# servo.net
KiCad netlist of a schematic drawn in EAGLE
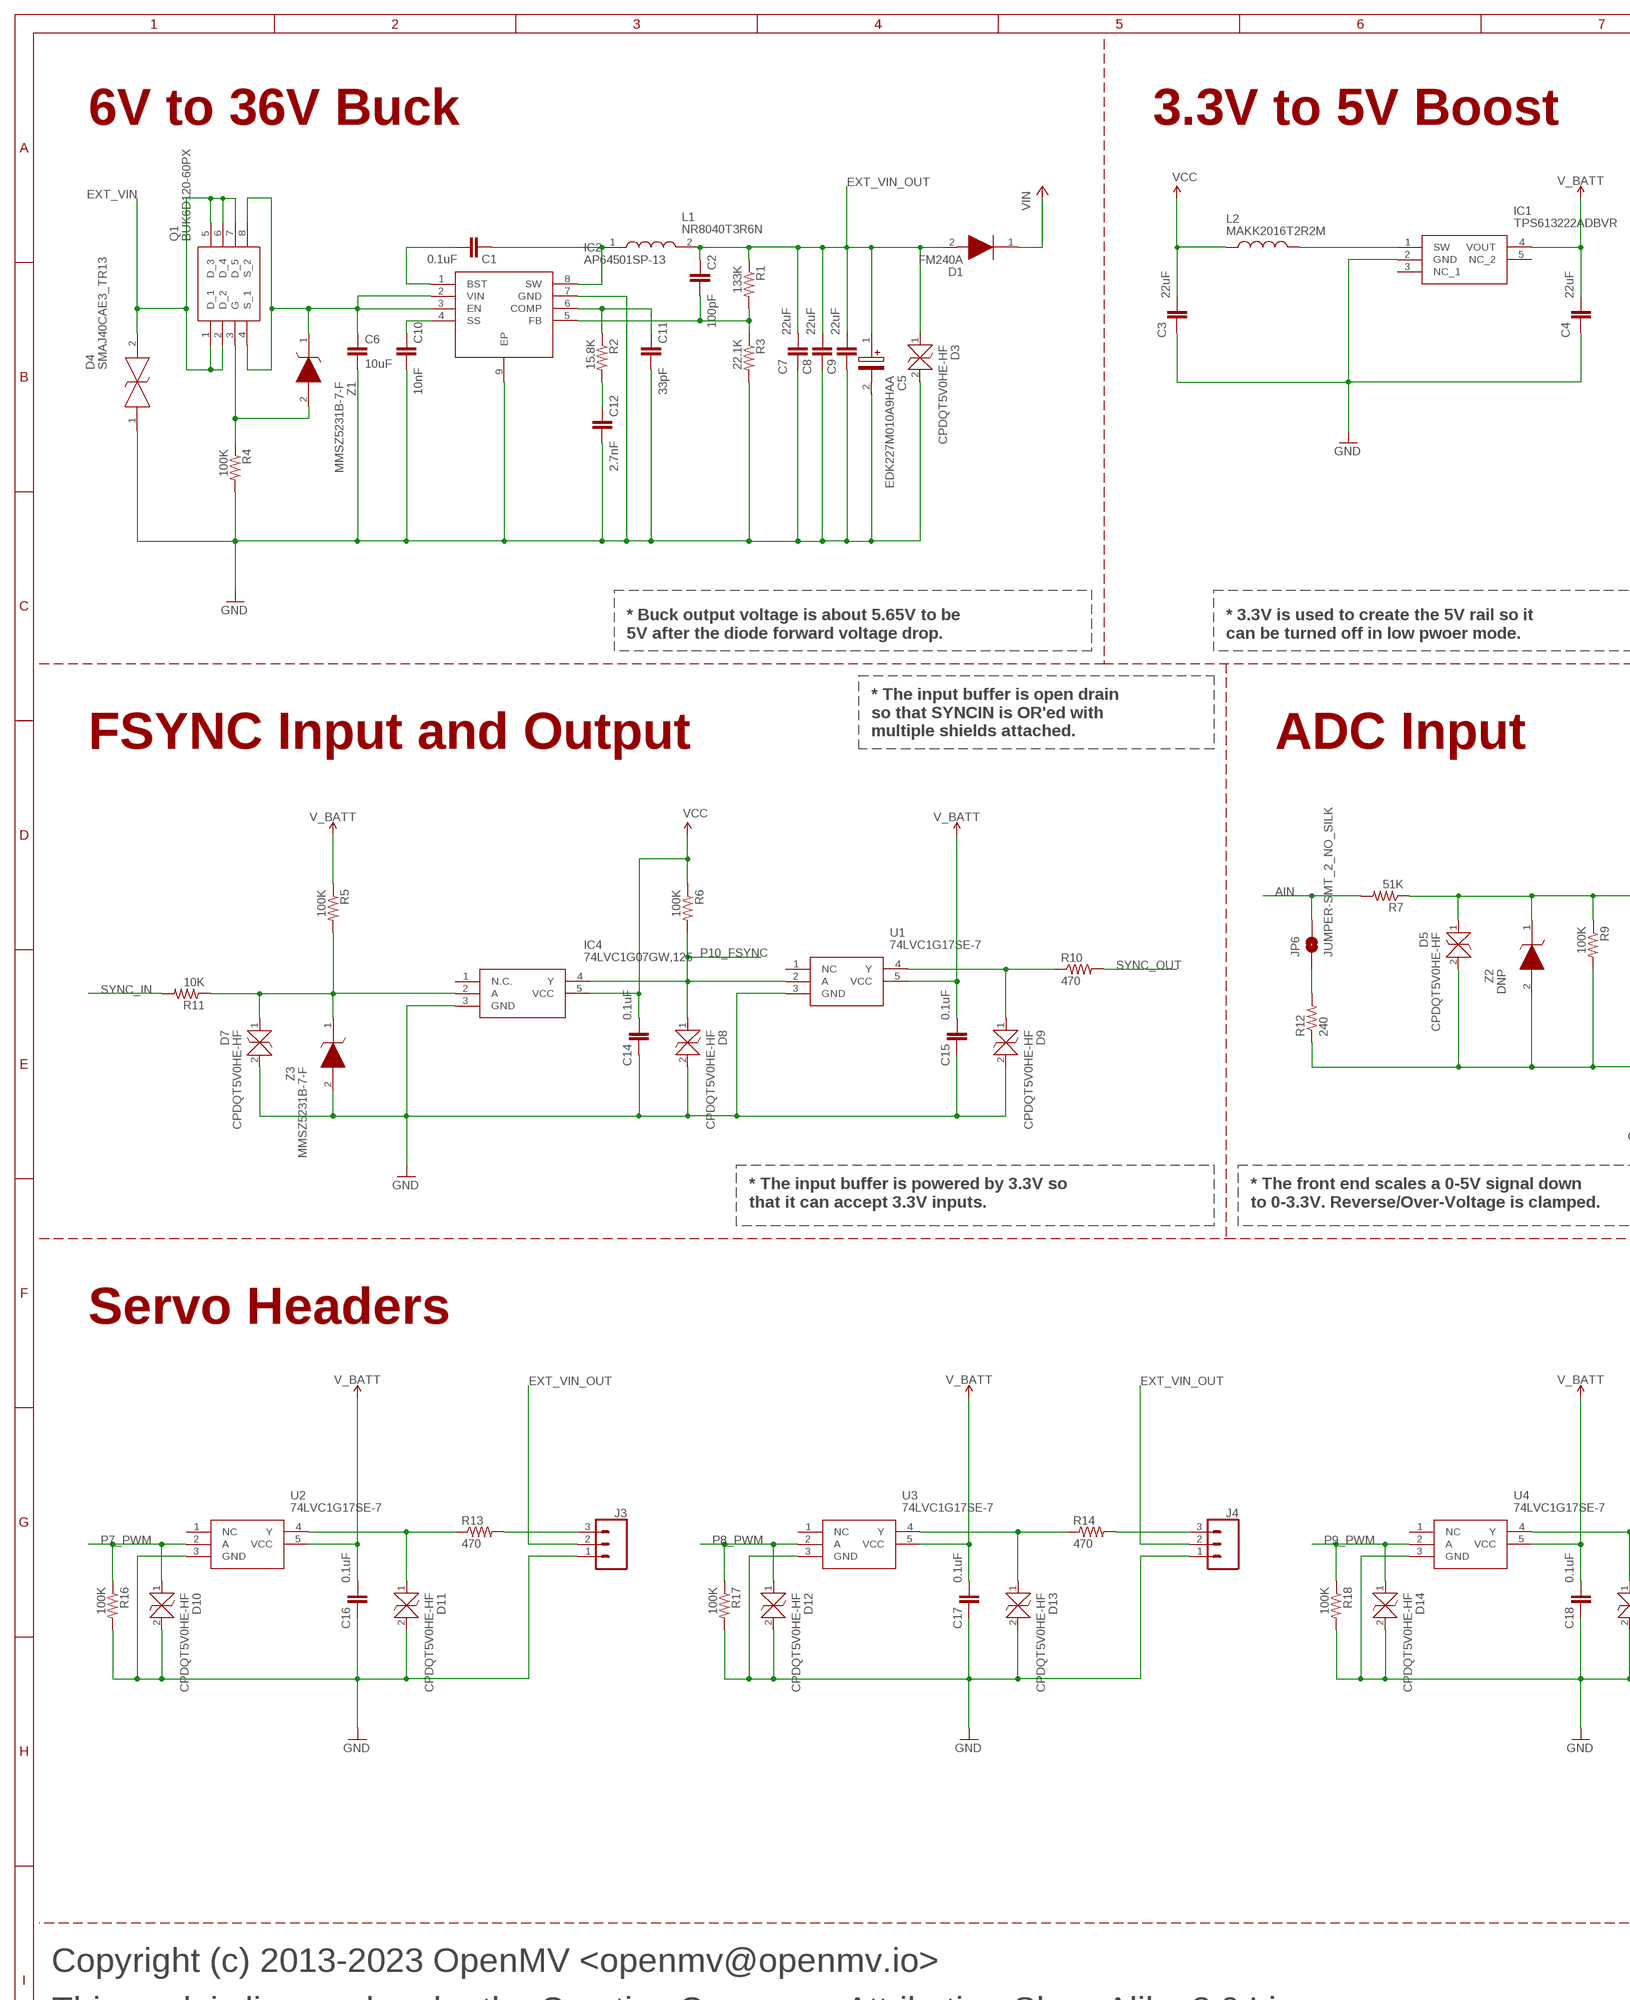
[diagram p0: schematic, sheet 1, part 1 of 2]
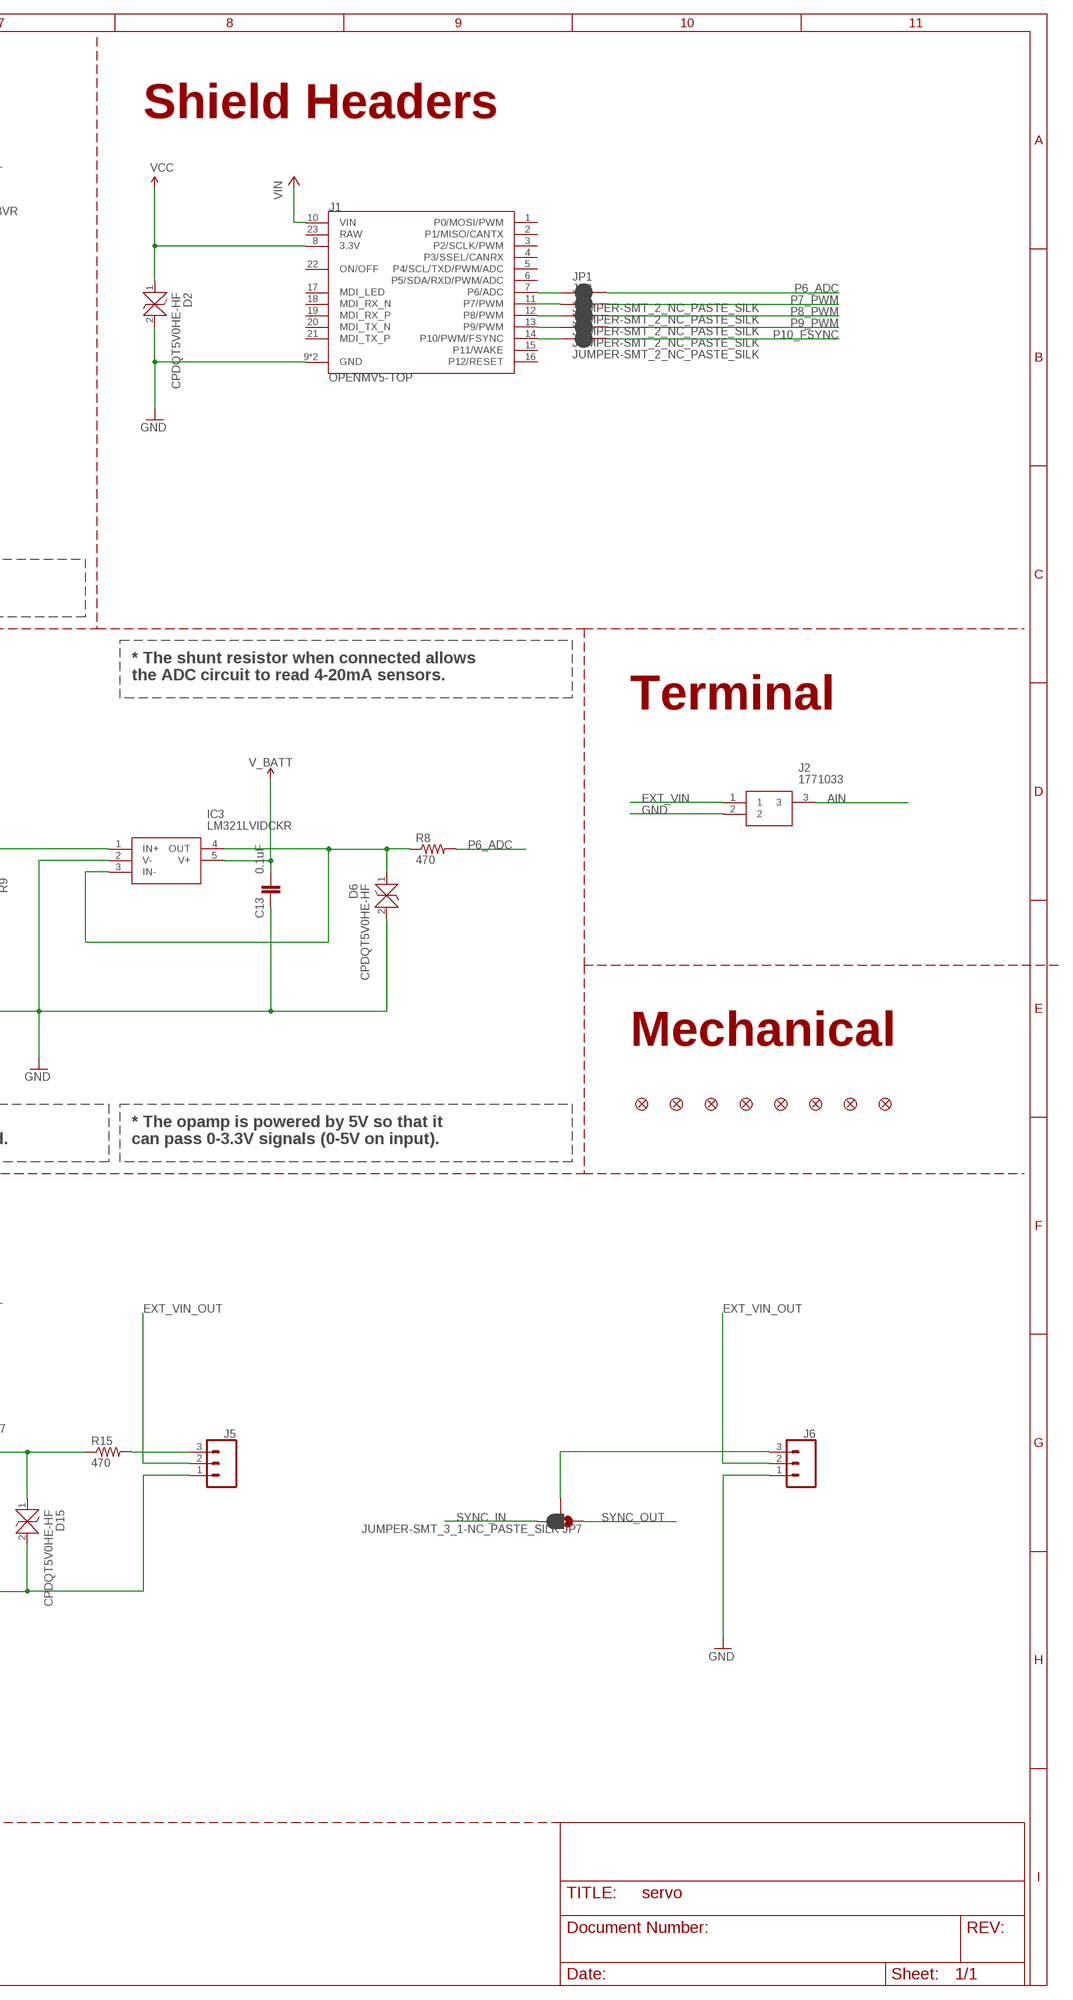
[diagram p1: schematic, sheet 1, part 2 of 2]

(export (version "E")
  (design (tool "Eeschema 10.0.6"))
  (components
    (comp (ref "C1")
      (value "0.1uF")
      (footprint "eagle-import:0402")
      (fields (field (name "MPN") "GRM155R71H104KE14D"))
      (libsource (lib "eagle-import") (part "CAP_0402"))
    )
    (comp (ref "C2")
      (value "100pF")
      (footprint "eagle-import:0402")
      (fields (field (name "MPN") "CC0402JRNPO9BN101"))
      (libsource (lib "eagle-import") (part "CAP_0402"))
    )
    (comp (ref "C3")
      (value "22uF")
      (footprint "eagle-import:0805")
      (fields (field (name "MPN") "CL21A226MQQNNNE"))
      (libsource (lib "eagle-import") (part "22UF-0805-6.3V-20%"))
    )
    (comp (ref "C4")
      (value "22uF")
      (footprint "eagle-import:0805")
      (fields (field (name "MPN") "CL21A226MQQNNNE"))
      (libsource (lib "eagle-import") (part "22UF-0805-6.3V-20%"))
    )
    (comp (ref "C5")
      (value "EDK227M010A9HAA")
      (footprint "eagle-import:CAPAE660X800N")
      (fields (field (name "MOUSER_PART_NUMBER") "80-EDK227M010A9HAA"))
      (libsource (lib "eagle-import") (part "EDK227M010A9HAA"))
    )
    (comp (ref "C6")
      (value "10uF")
      (footprint "eagle-import:C0805")
      (fields (field (name "MPN") "GRM21BR61H106KE43K"))
      (libsource (lib "eagle-import") (part "C-EUC0805"))
    )
    (comp (ref "C7")
      (value "22uF")
      (footprint "eagle-import:0805")
      (fields (field (name "MPN") "CL21A226MQQNNNE"))
      (libsource (lib "eagle-import") (part "22UF-0805-6.3V-20%"))
    )
    (comp (ref "C8")
      (value "22uF")
      (footprint "eagle-import:0805")
      (fields (field (name "MPN") "CL21A226MQQNNNE"))
      (libsource (lib "eagle-import") (part "22UF-0805-6.3V-20%"))
    )
    (comp (ref "C9")
      (value "22uF")
      (footprint "eagle-import:0805")
      (fields (field (name "MPN") "CL21A226MQQNNNE"))
      (libsource (lib "eagle-import") (part "22UF-0805-6.3V-20%"))
    )
    (comp (ref "C10")
      (value "10nF")
      (footprint "eagle-import:0402")
      (fields (field (name "MPN") "CL05B103KB5NNNC"))
      (libsource (lib "eagle-import") (part "CAP_0402"))
    )
    (comp (ref "C11")
      (value "33pF")
      (footprint "eagle-import:0402")
      (fields (field (name "MPN") "04025A330JAT2A"))
      (libsource (lib "eagle-import") (part "CAP_0402"))
    )
    (comp (ref "C12")
      (value "2.7nF")
      (footprint "eagle-import:0402")
      (fields (field (name "MPN") "GCM155R71H272KA37J"))
      (libsource (lib "eagle-import") (part "CAP_0402"))
    )
    (comp (ref "C13")
      (value "0.1uF")
      (footprint "eagle-import:0402")
      (fields (field (name "MPN") "GRM155R71H104KE14D"))
      (libsource (lib "eagle-import") (part "CAP_0402"))
    )
    (comp (ref "C14")
      (value "0.1uF")
      (footprint "eagle-import:0402")
      (fields (field (name "MPN") "GRM155R71H104KE14D"))
      (libsource (lib "eagle-import") (part "CAP_0402"))
    )
    (comp (ref "C15")
      (value "0.1uF")
      (footprint "eagle-import:0402")
      (fields (field (name "MPN") "GRM155R71H104KE14D"))
      (libsource (lib "eagle-import") (part "CAP_0402"))
    )
    (comp (ref "C16")
      (value "0.1uF")
      (footprint "eagle-import:0402")
      (fields (field (name "MPN") "GRM155R71H104KE14D"))
      (libsource (lib "eagle-import") (part "CAP_0402"))
    )
    (comp (ref "C17")
      (value "0.1uF")
      (footprint "eagle-import:0402")
      (fields (field (name "MPN") "GRM155R71H104KE14D"))
      (libsource (lib "eagle-import") (part "CAP_0402"))
    )
    (comp (ref "C18")
      (value "0.1uF")
      (footprint "eagle-import:0402")
      (fields (field (name "MPN") "GRM155R71H104KE14D"))
      (libsource (lib "eagle-import") (part "CAP_0402"))
    )
    (comp (ref "D1")
      (value "FM240A")
      (footprint "eagle-import:DIOM5025X231N")
      (fields (field (name "MOUSER_PART_NUMBER") "583-FM240A"))
      (libsource (lib "eagle-import") (part "FM240A"))
    )
    (comp (ref "D2")
      (value "CPDQT5V0HE-HF")
      (footprint "eagle-import:CPDQT5V0HEHF")
      (libsource (lib "eagle-import") (part "CPDQT5V0HE-HF"))
    )
    (comp (ref "D3")
      (value "CPDQT5V0HE-HF")
      (footprint "eagle-import:CPDQT5V0HEHF")
      (libsource (lib "eagle-import") (part "CPDQT5V0HE-HF"))
    )
    (comp (ref "D4")
      (value "SMAJ40CAE3_TR13")
      (footprint "eagle-import:SMAJ40CAE3TR13")
      (fields
        (field (name "MANUFACTURER_PART_NUMBER") "SMAJ40CAe3/TR13")
        (field (name "MOUSER_PART_NUMBER") "494-SMAJ40CAE3/TR13")
      )
      (libsource (lib "eagle-import") (part "SMAJ40CAE3_TR13"))
    )
    (comp (ref "D5")
      (value "CPDQT5V0HE-HF")
      (footprint "eagle-import:CPDQT5V0HEHF")
      (libsource (lib "eagle-import") (part "CPDQT5V0HE-HF"))
    )
    (comp (ref "D6")
      (value "CPDQT5V0HE-HF")
      (footprint "eagle-import:CPDQT5V0HEHF")
      (libsource (lib "eagle-import") (part "CPDQT5V0HE-HF"))
    )
    (comp (ref "D7")
      (value "CPDQT5V0HE-HF")
      (footprint "eagle-import:CPDQT5V0HEHF")
      (libsource (lib "eagle-import") (part "CPDQT5V0HE-HF"))
    )
    (comp (ref "D8")
      (value "CPDQT5V0HE-HF")
      (footprint "eagle-import:CPDQT5V0HEHF")
      (libsource (lib "eagle-import") (part "CPDQT5V0HE-HF"))
    )
    (comp (ref "D9")
      (value "CPDQT5V0HE-HF")
      (footprint "eagle-import:CPDQT5V0HEHF")
      (libsource (lib "eagle-import") (part "CPDQT5V0HE-HF"))
    )
    (comp (ref "D10")
      (value "CPDQT5V0HE-HF")
      (footprint "eagle-import:CPDQT5V0HEHF")
      (libsource (lib "eagle-import") (part "CPDQT5V0HE-HF"))
    )
    (comp (ref "D11")
      (value "CPDQT5V0HE-HF")
      (footprint "eagle-import:CPDQT5V0HEHF")
      (libsource (lib "eagle-import") (part "CPDQT5V0HE-HF"))
    )
    (comp (ref "D12")
      (value "CPDQT5V0HE-HF")
      (footprint "eagle-import:CPDQT5V0HEHF")
      (libsource (lib "eagle-import") (part "CPDQT5V0HE-HF"))
    )
    (comp (ref "D13")
      (value "CPDQT5V0HE-HF")
      (footprint "eagle-import:CPDQT5V0HEHF")
      (libsource (lib "eagle-import") (part "CPDQT5V0HE-HF"))
    )
    (comp (ref "D14")
      (value "CPDQT5V0HE-HF")
      (footprint "eagle-import:CPDQT5V0HEHF")
      (libsource (lib "eagle-import") (part "CPDQT5V0HE-HF"))
    )
    (comp (ref "D15")
      (value "CPDQT5V0HE-HF")
      (footprint "eagle-import:CPDQT5V0HEHF")
      (libsource (lib "eagle-import") (part "CPDQT5V0HE-HF"))
    )
    (comp (ref "FD1")
      (value "FIDUCIAL1X2")
      (footprint "eagle-import:FIDUCIAL-1X2")
      (libsource (lib "eagle-import") (part "FIDUCIAL1X2"))
    )
    (comp (ref "FD2")
      (value "FIDUCIAL1X2")
      (footprint "eagle-import:FIDUCIAL-1X2")
      (libsource (lib "eagle-import") (part "FIDUCIAL1X2"))
    )
    (comp (ref "FD3")
      (value "FIDUCIAL1X2")
      (footprint "eagle-import:FIDUCIAL-1X2")
      (libsource (lib "eagle-import") (part "FIDUCIAL1X2"))
    )
    (comp (ref "FD4")
      (value "FIDUCIAL1X2")
      (footprint "eagle-import:FIDUCIAL-1X2")
      (libsource (lib "eagle-import") (part "FIDUCIAL1X2"))
    )
    (comp (ref "FD5")
      (value "FIDUCIAL1X2")
      (footprint "eagle-import:FIDUCIAL-1X2")
      (libsource (lib "eagle-import") (part "FIDUCIAL1X2"))
    )
    (comp (ref "FD6")
      (value "FIDUCIAL1X2")
      (footprint "eagle-import:FIDUCIAL-1X2")
      (libsource (lib "eagle-import") (part "FIDUCIAL1X2"))
    )
    (comp (ref "FD7")
      (value "FIDUCIAL1X2")
      (footprint "eagle-import:FIDUCIAL-1X2")
      (libsource (lib "eagle-import") (part "FIDUCIAL1X2"))
    )
    (comp (ref "FD8")
      (value "FIDUCIAL1X2")
      (footprint "eagle-import:FIDUCIAL-1X2")
      (libsource (lib "eagle-import") (part "FIDUCIAL1X2"))
    )
    (comp (ref "IC1")
      (value "TPS613222ADBVR")
      (footprint "eagle-import:SOT95P280X145-5N")
      (fields (field (name "MOUSER_PART_NUMBER") "595-TPS613222ADBVR"))
      (libsource (lib "eagle-import") (part "TPS613222ADBVR"))
    )
    (comp (ref "IC2")
      (value "AP64501SP-13")
      (footprint "eagle-import:SOIC127P600X163-9N")
      (fields (field (name "MOUSER_PART_NUMBER") "621-AP64501SP-13"))
      (libsource (lib "eagle-import") (part "AP64501SP-13"))
    )
    (comp (ref "IC3")
      (value "LM321LVIDCKR")
      (footprint "eagle-import:SOT65P210X110-5N")
      (fields (field (name "MOUSER_PART_NUMBER") "595-LM321LVIDCKR"))
      (libsource (lib "eagle-import") (part "LM321LVIDCKR"))
    )
    (comp (ref "IC4")
      (value "74LVC1G07GW,125")
      (footprint "eagle-import:SOT65P212X110-5N")
      (fields (field (name "MOUSER_PART_NUMBER") "771-74LVC1G07GW-G"))
      (libsource (lib "eagle-import") (part "74LVC1G07GW,125"))
    )
    (comp (ref "J1")
      (value "OPENMV5-TOP")
      (footprint "eagle-import:OPENMV5-TOP")
      (libsource (lib "eagle-import") (part "OPENMV5-TOP"))
    )
    (comp (ref "J2")
      (value "1771033")
      (footprint "eagle-import:1771033")
      (fields (field (name "MOUSER_PART_NUMBER") "651-1771033"))
      (libsource (lib "eagle-import") (part "1771033"))
    )
    (comp (ref "J3")
      (value "CONN_03")
      (footprint "eagle-import:1X03")
      (libsource (lib "eagle-import") (part "CONN_03"))
    )
    (comp (ref "J4")
      (value "CONN_03")
      (footprint "eagle-import:1X03")
      (libsource (lib "eagle-import") (part "CONN_03"))
    )
    (comp (ref "J5")
      (value "CONN_03")
      (footprint "eagle-import:1X03")
      (libsource (lib "eagle-import") (part "CONN_03"))
    )
    (comp (ref "J6")
      (value "CONN_03")
      (footprint "eagle-import:1X03")
      (libsource (lib "eagle-import") (part "CONN_03"))
    )
    (comp (ref "JP1")
      (value "JUMPER-SMT_2_NC_PASTE_SILK")
      (footprint "eagle-import:SMT-JUMPER_2_NC_PASTE_SILK")
      (libsource (lib "eagle-import") (part "JUMPER-SMT_2_NC_PASTE_SILK"))
    )
    (comp (ref "JP2")
      (value "JUMPER-SMT_2_NC_PASTE_SILK")
      (footprint "eagle-import:SMT-JUMPER_2_NC_PASTE_SILK")
      (libsource (lib "eagle-import") (part "JUMPER-SMT_2_NC_PASTE_SILK"))
    )
    (comp (ref "JP3")
      (value "JUMPER-SMT_2_NC_PASTE_SILK")
      (footprint "eagle-import:SMT-JUMPER_2_NC_PASTE_SILK")
      (libsource (lib "eagle-import") (part "JUMPER-SMT_2_NC_PASTE_SILK"))
    )
    (comp (ref "JP4")
      (value "JUMPER-SMT_2_NC_PASTE_SILK")
      (footprint "eagle-import:SMT-JUMPER_2_NC_PASTE_SILK")
      (libsource (lib "eagle-import") (part "JUMPER-SMT_2_NC_PASTE_SILK"))
    )
    (comp (ref "JP5")
      (value "JUMPER-SMT_2_NC_PASTE_SILK")
      (footprint "eagle-import:SMT-JUMPER_2_NC_PASTE_SILK")
      (libsource (lib "eagle-import") (part "JUMPER-SMT_2_NC_PASTE_SILK"))
    )
    (comp (ref "JP6")
      (value "JUMPER-SMT_2_NO_SILK")
      (footprint "eagle-import:SMT-JUMPER_2_NO_SILK")
      (libsource (lib "eagle-import") (part "JUMPER-SMT_2_NO_SILK"))
    )
    (comp (ref "JP7")
      (value "JUMPER-SMT_3_1-NC_PASTE_SILK")
      (footprint "eagle-import:SMT-JUMPER_3_1-NC_PASTE_SILK")
      (libsource (lib "eagle-import") (part "JUMPER-SMT_3_1-NC_PASTE_SILK"))
    )
    (comp (ref "L1")
      (value "NR8040T3R6N")
      (footprint "eagle-import:NR8040T3R6N")
      (fields (field (name "MOUSER_PART_NUMBER") "963-NR8040T3R6N") (field (name "MPN") "NRS8040T3R6NJGJ"))
      (libsource (lib "eagle-import") (part "NR8040T3R6N"))
    )
    (comp (ref "L2")
      (value "MAKK2016T2R2M")
      (footprint "eagle-import:INDC2016X100N")
      (fields (field (name "MF") "Taiyo Yuden"))
      (libsource (lib "eagle-import") (part "MAKK2016T2R2M"))
    )
    (comp (ref "Q1")
      (value "BUK6D120-60PX")
      (footprint "eagle-import:BUK6D12060PX")
      (fields (field (name "MOUSER_PART_NUMBER") "771-BUK6D120-60PX"))
      (libsource (lib "eagle-import") (part "BUK6D120-60PX"))
    )
    (comp (ref "R1")
      (value "133K")
      (footprint "eagle-import:0402")
      (fields (field (name "MPN") "RC0402FR-07133KL"))
      (libsource (lib "eagle-import") (part "RES_0402"))
    )
    (comp (ref "R2")
      (value "15.8K")
      (footprint "eagle-import:0402")
      (fields (field (name "MPN") "AC0402FR-0715K8L"))
      (libsource (lib "eagle-import") (part "RES_0402"))
    )
    (comp (ref "R3")
      (value "22.1K")
      (footprint "eagle-import:0402")
      (fields (field (name "MPN") "CR0402-FX-2212GLF"))
      (libsource (lib "eagle-import") (part "RES_0402"))
    )
    (comp (ref "R4")
      (value "100K")
      (footprint "eagle-import:0402")
      (fields (field (name "MPN") "AC0402FR-07100KL"))
      (libsource (lib "eagle-import") (part "RES_0402"))
    )
    (comp (ref "R5")
      (value "100K")
      (footprint "eagle-import:0402")
      (fields (field (name "MPN") "AC0402FR-07100KL"))
      (libsource (lib "eagle-import") (part "RES_0402"))
    )
    (comp (ref "R6")
      (value "100K")
      (footprint "eagle-import:0402")
      (fields (field (name "MPN") "AC0402FR-07100KL"))
      (libsource (lib "eagle-import") (part "RES_0402"))
    )
    (comp (ref "R7")
      (value "51K")
      (footprint "eagle-import:0402")
      (fields (field (name "MPN") "RC0402JR-0751KL"))
      (libsource (lib "eagle-import") (part "RES_0402"))
    )
    (comp (ref "R8")
      (value "470")
      (footprint "eagle-import:R0603")
      (fields (field (name "MPN") "CR0603-FX-4700ELF"))
      (libsource (lib "eagle-import") (part "R-US_R0603"))
    )
    (comp (ref "R9")
      (value "100K")
      (footprint "eagle-import:0402")
      (fields (field (name "MPN") "AC0402FR-07100KL"))
      (libsource (lib "eagle-import") (part "RES_0402"))
    )
    (comp (ref "R10")
      (value "470")
      (footprint "eagle-import:R0603")
      (fields (field (name "MPN") "CR0603-FX-4700ELF"))
      (libsource (lib "eagle-import") (part "R-US_R0603"))
    )
    (comp (ref "R11")
      (value "10K")
      (footprint "eagle-import:0402")
      (fields (field (name "MPN") "AC0402FR-1310KL"))
      (libsource (lib "eagle-import") (part "RES_0402"))
    )
    (comp (ref "R12")
      (value "240")
      (footprint "eagle-import:R0603")
      (fields (field (name "MPN") "RK73B1JTTD241J"))
      (libsource (lib "eagle-import") (part "R-US_R0603"))
    )
    (comp (ref "R13")
      (value "470")
      (footprint "eagle-import:R0603")
      (fields (field (name "MPN") "CR0603-FX-4700ELF"))
      (libsource (lib "eagle-import") (part "R-US_R0603"))
    )
    (comp (ref "R14")
      (value "470")
      (footprint "eagle-import:R0603")
      (fields (field (name "MPN") "CR0603-FX-4700ELF"))
      (libsource (lib "eagle-import") (part "R-US_R0603"))
    )
    (comp (ref "R15")
      (value "470")
      (footprint "eagle-import:R0603")
      (fields (field (name "MPN") "CR0603-FX-4700ELF"))
      (libsource (lib "eagle-import") (part "R-US_R0603"))
    )
    (comp (ref "R16")
      (value "100K")
      (footprint "eagle-import:0402")
      (fields (field (name "MPN") "AC0402FR-07100KL"))
      (libsource (lib "eagle-import") (part "RES_0402"))
    )
    (comp (ref "R17")
      (value "100K")
      (footprint "eagle-import:0402")
      (fields (field (name "MPN") "AC0402FR-07100KL"))
      (libsource (lib "eagle-import") (part "RES_0402"))
    )
    (comp (ref "R18")
      (value "100K")
      (footprint "eagle-import:0402")
      (fields (field (name "MPN") "AC0402FR-07100KL"))
      (libsource (lib "eagle-import") (part "RES_0402"))
    )
    (comp (ref "U1")
      (value "74LVC1G17SE-7")
      (footprint "eagle-import:SOT65P210X110-5N")
      (fields (field (name "MOUSER_PART_NUMBER") "621-74LVC1G17SE-7"))
      (libsource (lib "eagle-import") (part "74LVC1G17SE-7"))
    )
    (comp (ref "U2")
      (value "74LVC1G17SE-7")
      (footprint "eagle-import:SOT65P210X110-5N")
      (fields (field (name "MOUSER_PART_NUMBER") "621-74LVC1G17SE-7"))
      (libsource (lib "eagle-import") (part "74LVC1G17SE-7"))
    )
    (comp (ref "U3")
      (value "74LVC1G17SE-7")
      (footprint "eagle-import:SOT65P210X110-5N")
      (fields (field (name "MOUSER_PART_NUMBER") "621-74LVC1G17SE-7"))
      (libsource (lib "eagle-import") (part "74LVC1G17SE-7"))
    )
    (comp (ref "U4")
      (value "74LVC1G17SE-7")
      (footprint "eagle-import:SOT65P210X110-5N")
      (fields (field (name "MOUSER_PART_NUMBER") "621-74LVC1G17SE-7"))
      (libsource (lib "eagle-import") (part "74LVC1G17SE-7"))
    )
    (comp (ref "Z1")
      (value "MMSZ5231B-7-F")
      (footprint "eagle-import:SOD3716X145N")
      (fields (field (name "MOUSER_PART_NUMBER") "621-MMSZ5231B-F"))
      (libsource (lib "eagle-import") (part "MMSZ5231B-7-F"))
    )
    (comp (ref "Z2")
      (value "DNP")
      (footprint "eagle-import:SOD2512X110N")
      (fields
        (field (name "MANUFACTURER_PART_NUMBER") "MM3Z3V6T1G")
        (field (name "MOUSER_PART_NUMBER") "863-MM3Z3V6T1G")
      )
      (libsource (lib "eagle-import") (part "MM3Z3V6T1G"))
    )
    (comp (ref "Z3")
      (value "MMSZ5231B-7-F")
      (footprint "eagle-import:SOD3716X145N")
      (fields (field (name "MOUSER_PART_NUMBER") "621-MMSZ5231B-F"))
      (libsource (lib "eagle-import") (part "MMSZ5231B-7-F"))
    )
  )
  (nets
    (net (code "1") (name "/AIN") (class "Default")
      (node (ref "J2") (pin "3") (pinfunction "3_3") (pintype "bidirectional"))
      (node (ref "JP6") (pin "2") (pinfunction "2_2") (pintype "passive"))
      (node (ref "R7") (pin "2") (pinfunction "2_2") (pintype "passive"))
    )
    (net (code "2") (name "/EXT_VIN") (class "Default")
      (node (ref "D4") (pin "2") (pinfunction "2_2") (pintype "bidirectional"))
      (node (ref "J2") (pin "1") (pinfunction "1_1") (pintype "bidirectional"))
      (node (ref "Q1") (pin "1") (pinfunction "D_1_1") (pintype "bidirectional"))
      (node (ref "Q1") (pin "2") (pinfunction "D_2_2") (pintype "bidirectional"))
      (node (ref "Q1") (pin "5") (pinfunction "D_3_5") (pintype "bidirectional"))
      (node (ref "Q1") (pin "6") (pinfunction "D_4_6") (pintype "bidirectional"))
      (node (ref "Q1") (pin "7") (pinfunction "D_5_7") (pintype "bidirectional"))
    )
    (net (code "3") (name "/EXT_VIN_OUT") (class "Default")
      (node (ref "C2") (pin "1") (pinfunction "1_1") (pintype "passive"))
      (node (ref "C5") (pin "1") (pinfunction "+_1") (pintype "bidirectional"))
      (node (ref "C7") (pin "2") (pinfunction "2_2") (pintype "passive"))
      (node (ref "C8") (pin "2") (pinfunction "2_2") (pintype "passive"))
      (node (ref "C9") (pin "2") (pinfunction "2_2") (pintype "passive"))
      (node (ref "D1") (pin "2") (pinfunction "A_2") (pintype "bidirectional"))
      (node (ref "D3") (pin "1") (pinfunction "1_1") (pintype "bidirectional"))
      (node (ref "J3") (pin "2") (pinfunction "2_2") (pintype "passive"))
      (node (ref "J4") (pin "2") (pinfunction "2_2") (pintype "passive"))
      (node (ref "J5") (pin "2") (pinfunction "2_2") (pintype "passive"))
      (node (ref "J6") (pin "2") (pinfunction "2_2") (pintype "passive"))
      (node (ref "L1") (pin "2") (pinfunction "2_2") (pintype "bidirectional"))
      (node (ref "R1") (pin "1") (pinfunction "1_1") (pintype "passive"))
    )
    (net (code "4") (name "/P6_ADC") (class "Default")
      (node (ref "JP1") (pin "2") (pinfunction "2_2") (pintype "passive"))
      (node (ref "R8") (pin "2") (pinfunction "2_2") (pintype "passive"))
    )
    (net (code "5") (name "/P7_PWM") (class "Default")
      (node (ref "D10") (pin "1") (pinfunction "1_1") (pintype "bidirectional"))
      (node (ref "JP2") (pin "2") (pinfunction "2_2") (pintype "passive"))
      (node (ref "R16") (pin "1") (pinfunction "1_1") (pintype "passive"))
      (node (ref "U2") (pin "2") (pinfunction "A_2") (pintype "bidirectional"))
    )
    (net (code "6") (name "/P8_PWM") (class "Default")
      (node (ref "D12") (pin "1") (pinfunction "1_1") (pintype "bidirectional"))
      (node (ref "JP3") (pin "2") (pinfunction "2_2") (pintype "passive"))
      (node (ref "R17") (pin "1") (pinfunction "1_1") (pintype "passive"))
      (node (ref "U3") (pin "2") (pinfunction "A_2") (pintype "bidirectional"))
    )
    (net (code "7") (name "/P9_PWM") (class "Default")
      (node (ref "D14") (pin "1") (pinfunction "1_1") (pintype "bidirectional"))
      (node (ref "JP4") (pin "2") (pinfunction "2_2") (pintype "passive"))
      (node (ref "R18") (pin "1") (pinfunction "1_1") (pintype "passive"))
      (node (ref "U4") (pin "2") (pinfunction "A_2") (pintype "bidirectional"))
    )
    (net (code "8") (name "/P10_FSYNC") (class "Default")
      (node (ref "D8") (pin "1") (pinfunction "1_1") (pintype "bidirectional"))
      (node (ref "IC4") (pin "4") (pinfunction "Y_4") (pintype "bidirectional"))
      (node (ref "JP5") (pin "2") (pinfunction "2_2") (pintype "passive"))
      (node (ref "R6") (pin "2") (pinfunction "2_2") (pintype "passive"))
      (node (ref "U1") (pin "2") (pinfunction "A_2") (pintype "bidirectional"))
    )
    (net (code "9") (name "/RAW") (class "Default")
      (node (ref "J1") (pin "23") (pinfunction "RAW_23") (pintype "power_in"))
    )
    (net (code "10") (name "/SYNC_IN") (class "Default")
      (node (ref "JP7") (pin "3") (pinfunction "3_3") (pintype "passive"))
      (node (ref "R11") (pin "2") (pinfunction "2_2") (pintype "passive"))
    )
    (net (code "11") (name "/SYNC_OUT") (class "Default")
      (node (ref "JP7") (pin "1") (pinfunction "1_1") (pintype "passive"))
      (node (ref "R10") (pin "2") (pinfunction "2_2") (pintype "passive"))
    )
    (net (code "12") (name "GND") (class "Default")
      (node (ref "C10") (pin "2") (pinfunction "2_2") (pintype "passive"))
      (node (ref "C11") (pin "2") (pinfunction "2_2") (pintype "passive"))
      (node (ref "C12") (pin "2") (pinfunction "2_2") (pintype "passive"))
      (node (ref "C13") (pin "1") (pinfunction "1_1") (pintype "passive"))
      (node (ref "C14") (pin "1") (pinfunction "1_1") (pintype "passive"))
      (node (ref "C15") (pin "1") (pinfunction "1_1") (pintype "passive"))
      (node (ref "C16") (pin "1") (pinfunction "1_1") (pintype "passive"))
      (node (ref "C17") (pin "1") (pinfunction "1_1") (pintype "passive"))
      (node (ref "C18") (pin "1") (pinfunction "1_1") (pintype "passive"))
      (node (ref "C3") (pin "1") (pinfunction "1_1") (pintype "passive"))
      (node (ref "C4") (pin "1") (pinfunction "1_1") (pintype "passive"))
      (node (ref "C5") (pin "2") (pinfunction "-_2") (pintype "bidirectional"))
      (node (ref "C6") (pin "2") (pinfunction "2_2") (pintype "passive"))
      (node (ref "C7") (pin "1") (pinfunction "1_1") (pintype "passive"))
      (node (ref "C8") (pin "1") (pinfunction "1_1") (pintype "passive"))
      (node (ref "C9") (pin "1") (pinfunction "1_1") (pintype "passive"))
      (node (ref "D10") (pin "2") (pinfunction "2_2") (pintype "bidirectional"))
      (node (ref "D11") (pin "2") (pinfunction "2_2") (pintype "bidirectional"))
      (node (ref "D12") (pin "2") (pinfunction "2_2") (pintype "bidirectional"))
      (node (ref "D13") (pin "2") (pinfunction "2_2") (pintype "bidirectional"))
      (node (ref "D14") (pin "2") (pinfunction "2_2") (pintype "bidirectional"))
      (node (ref "D15") (pin "2") (pinfunction "2_2") (pintype "bidirectional"))
      (node (ref "D2") (pin "2") (pinfunction "2_2") (pintype "bidirectional"))
      (node (ref "D3") (pin "2") (pinfunction "2_2") (pintype "bidirectional"))
      (node (ref "D4") (pin "1") (pinfunction "1_1") (pintype "bidirectional"))
      (node (ref "D5") (pin "2") (pinfunction "2_2") (pintype "bidirectional"))
      (node (ref "D6") (pin "2") (pinfunction "2_2") (pintype "bidirectional"))
      (node (ref "D7") (pin "2") (pinfunction "2_2") (pintype "bidirectional"))
      (node (ref "D8") (pin "2") (pinfunction "2_2") (pintype "bidirectional"))
      (node (ref "D9") (pin "2") (pinfunction "2_2") (pintype "bidirectional"))
      (node (ref "IC1") (pin "2") (pinfunction "GND_2") (pintype "bidirectional"))
      (node (ref "IC2") (pin "7") (pinfunction "GND_7") (pintype "bidirectional"))
      (node (ref "IC2") (pin "9") (pinfunction "EP_9") (pintype "bidirectional"))
      (node (ref "IC3") (pin "2") (pinfunction "V-_2") (pintype "input"))
      (node (ref "IC4") (pin "3") (pinfunction "GND_3") (pintype "bidirectional"))
      (node (ref "J1") (pin "24") (pinfunction "GND_24") (pintype "power_in"))
      (node (ref "J1") (pin "9") (pinfunction "GND_9") (pintype "power_in"))
      (node (ref "J2") (pin "2") (pinfunction "2_2") (pintype "bidirectional"))
      (node (ref "J3") (pin "1") (pinfunction "1_1") (pintype "passive"))
      (node (ref "J4") (pin "1") (pinfunction "1_1") (pintype "passive"))
      (node (ref "J5") (pin "1") (pinfunction "1_1") (pintype "passive"))
      (node (ref "J6") (pin "1") (pinfunction "1_1") (pintype "passive"))
      (node (ref "R12") (pin "1") (pinfunction "1_1") (pintype "passive"))
      (node (ref "R16") (pin "2") (pinfunction "2_2") (pintype "passive"))
      (node (ref "R17") (pin "2") (pinfunction "2_2") (pintype "passive"))
      (node (ref "R18") (pin "2") (pinfunction "2_2") (pintype "passive"))
      (node (ref "R3") (pin "2") (pinfunction "2_2") (pintype "passive"))
      (node (ref "R4") (pin "2") (pinfunction "2_2") (pintype "passive"))
      (node (ref "R9") (pin "2") (pinfunction "2_2") (pintype "passive"))
      (node (ref "U1") (pin "3") (pinfunction "GND_3") (pintype "bidirectional"))
      (node (ref "U2") (pin "3") (pinfunction "GND_3") (pintype "bidirectional"))
      (node (ref "U3") (pin "3") (pinfunction "GND_3") (pintype "bidirectional"))
      (node (ref "U4") (pin "3") (pinfunction "GND_3") (pintype "bidirectional"))
      (node (ref "Z2") (pin "2") (pinfunction "A_2") (pintype "bidirectional"))
      (node (ref "Z3") (pin "2") (pinfunction "A_2") (pintype "bidirectional"))
    )
    (net (code "13") (name "Net-(C12-Pad1)") (class "Default")
      (node (ref "C12") (pin "1") (pinfunction "1_1") (pintype "passive"))
      (node (ref "R2") (pin "2") (pinfunction "2_2") (pintype "passive"))
    )
    (net (code "14") (name "Net-(IC1-SW)") (class "Default")
      (node (ref "IC1") (pin "1") (pinfunction "SW_1") (pintype "bidirectional"))
      (node (ref "L2") (pin "2") (pinfunction "2_2") (pintype "passive"))
    )
    (net (code "15") (name "Net-(IC2-BST)") (class "Default")
      (node (ref "C1") (pin "2") (pinfunction "2_2") (pintype "passive"))
      (node (ref "IC2") (pin "1") (pinfunction "BST_1") (pintype "bidirectional"))
    )
    (net (code "16") (name "Net-(IC2-COMP)") (class "Default")
      (node (ref "C11") (pin "1") (pinfunction "1_1") (pintype "passive"))
      (node (ref "IC2") (pin "6") (pinfunction "COMP_6") (pintype "bidirectional"))
      (node (ref "R2") (pin "1") (pinfunction "1_1") (pintype "passive"))
    )
    (net (code "17") (name "Net-(IC2-EN)") (class "Default")
      (node (ref "C6") (pin "1") (pinfunction "1_1") (pintype "passive"))
      (node (ref "IC2") (pin "2") (pinfunction "VIN_2") (pintype "bidirectional"))
      (node (ref "IC2") (pin "3") (pinfunction "EN_3") (pintype "bidirectional"))
      (node (ref "Q1") (pin "4") (pinfunction "S_1_4") (pintype "bidirectional"))
      (node (ref "Q1") (pin "8") (pinfunction "S_2_8") (pintype "bidirectional"))
      (node (ref "Z1") (pin "1") (pinfunction "K_1") (pintype "bidirectional"))
    )
    (net (code "18") (name "Net-(IC2-FB)") (class "Default")
      (node (ref "C2") (pin "2") (pinfunction "2_2") (pintype "passive"))
      (node (ref "IC2") (pin "5") (pinfunction "FB_5") (pintype "bidirectional"))
      (node (ref "R1") (pin "2") (pinfunction "2_2") (pintype "passive"))
      (node (ref "R3") (pin "1") (pinfunction "1_1") (pintype "passive"))
    )
    (net (code "19") (name "Net-(IC2-SS)") (class "Default")
      (node (ref "C10") (pin "1") (pinfunction "1_1") (pintype "passive"))
      (node (ref "IC2") (pin "4") (pinfunction "SS_4") (pintype "bidirectional"))
    )
    (net (code "20") (name "Net-(IC2-SW)") (class "Default")
      (node (ref "C1") (pin "1") (pinfunction "1_1") (pintype "passive"))
      (node (ref "IC2") (pin "8") (pinfunction "SW_8") (pintype "bidirectional"))
      (node (ref "L1") (pin "1") (pinfunction "1_1") (pintype "bidirectional"))
    )
    (net (code "21") (name "Net-(IC3-IN+)") (class "Default")
      (node (ref "D5") (pin "1") (pinfunction "1_1") (pintype "bidirectional"))
      (node (ref "IC3") (pin "1") (pinfunction "IN+_1") (pintype "input"))
      (node (ref "R7") (pin "1") (pinfunction "1_1") (pintype "passive"))
      (node (ref "R9") (pin "1") (pinfunction "1_1") (pintype "passive"))
      (node (ref "Z2") (pin "1") (pinfunction "K_1") (pintype "bidirectional"))
    )
    (net (code "22") (name "Net-(IC3-IN-)") (class "Default")
      (node (ref "D6") (pin "1") (pinfunction "1_1") (pintype "bidirectional"))
      (node (ref "IC3") (pin "3") (pinfunction "IN-_3") (pintype "input"))
      (node (ref "IC3") (pin "4") (pinfunction "OUT_4") (pintype "output"))
      (node (ref "R8") (pin "1") (pinfunction "1_1") (pintype "passive"))
    )
    (net (code "23") (name "Net-(IC4-A)") (class "Default")
      (node (ref "D7") (pin "1") (pinfunction "1_1") (pintype "bidirectional"))
      (node (ref "IC4") (pin "2") (pinfunction "A_2") (pintype "bidirectional"))
      (node (ref "R11") (pin "1") (pinfunction "1_1") (pintype "passive"))
      (node (ref "R5") (pin "2") (pinfunction "2_2") (pintype "passive"))
      (node (ref "Z3") (pin "1") (pinfunction "K_1") (pintype "bidirectional"))
    )
    (net (code "24") (name "Net-(J1-P6{slash}ADC)") (class "Default")
      (node (ref "J1") (pin "7") (pinfunction "P6/ADC_7") (pintype "bidirectional"))
      (node (ref "JP1") (pin "1") (pinfunction "1_1") (pintype "passive"))
    )
    (net (code "25") (name "Net-(J1-P7{slash}PWM)") (class "Default")
      (node (ref "J1") (pin "11") (pinfunction "P7/PWM_11") (pintype "bidirectional"))
      (node (ref "JP2") (pin "1") (pinfunction "1_1") (pintype "passive"))
    )
    (net (code "26") (name "Net-(J1-P8{slash}PWM)") (class "Default")
      (node (ref "J1") (pin "12") (pinfunction "P8/PWM_12") (pintype "bidirectional"))
      (node (ref "JP3") (pin "1") (pinfunction "1_1") (pintype "passive"))
    )
    (net (code "27") (name "Net-(J1-P9{slash}PWM)") (class "Default")
      (node (ref "J1") (pin "13") (pinfunction "P9/PWM_13") (pintype "bidirectional"))
      (node (ref "JP4") (pin "1") (pinfunction "1_1") (pintype "passive"))
    )
    (net (code "28") (name "Net-(J1-P10{slash}PWM{slash}FSYNC)") (class "Default")
      (node (ref "J1") (pin "14") (pinfunction "P10/PWM/FSYNC_14") (pintype "bidirectional"))
      (node (ref "JP5") (pin "1") (pinfunction "1_1") (pintype "passive"))
    )
    (net (code "29") (name "Net-(J3-Pad3)") (class "Default")
      (node (ref "J3") (pin "3") (pinfunction "3_3") (pintype "passive"))
      (node (ref "R13") (pin "2") (pinfunction "2_2") (pintype "passive"))
    )
    (net (code "30") (name "Net-(J4-Pad3)") (class "Default")
      (node (ref "J4") (pin "3") (pinfunction "3_3") (pintype "passive"))
      (node (ref "R14") (pin "2") (pinfunction "2_2") (pintype "passive"))
    )
    (net (code "31") (name "Net-(J5-Pad3)") (class "Default")
      (node (ref "J5") (pin "3") (pinfunction "3_3") (pintype "passive"))
      (node (ref "R15") (pin "2") (pinfunction "2_2") (pintype "passive"))
    )
    (net (code "32") (name "Net-(J6-Pad3)") (class "Default")
      (node (ref "J6") (pin "3") (pinfunction "3_3") (pintype "passive"))
      (node (ref "JP7") (pin "2") (pinfunction "2_2") (pintype "passive"))
    )
    (net (code "33") (name "Net-(JP6-Pad1)") (class "Default")
      (node (ref "JP6") (pin "1") (pinfunction "1_1") (pintype "passive"))
      (node (ref "R12") (pin "2") (pinfunction "2_2") (pintype "passive"))
    )
    (net (code "34") (name "Net-(Q1-G)") (class "Default")
      (node (ref "Q1") (pin "3") (pinfunction "G_3") (pintype "bidirectional"))
      (node (ref "R4") (pin "1") (pinfunction "1_1") (pintype "passive"))
      (node (ref "Z1") (pin "2") (pinfunction "A_2") (pintype "bidirectional"))
    )
    (net (code "35") (name "Net-(U1-Y)") (class "Default")
      (node (ref "D9") (pin "1") (pinfunction "1_1") (pintype "bidirectional"))
      (node (ref "R10") (pin "1") (pinfunction "1_1") (pintype "passive"))
      (node (ref "U1") (pin "4") (pinfunction "Y_4") (pintype "bidirectional"))
    )
    (net (code "36") (name "Net-(U2-Y)") (class "Default")
      (node (ref "D11") (pin "1") (pinfunction "1_1") (pintype "bidirectional"))
      (node (ref "R13") (pin "1") (pinfunction "1_1") (pintype "passive"))
      (node (ref "U2") (pin "4") (pinfunction "Y_4") (pintype "bidirectional"))
    )
    (net (code "37") (name "Net-(U3-Y)") (class "Default")
      (node (ref "D13") (pin "1") (pinfunction "1_1") (pintype "bidirectional"))
      (node (ref "R14") (pin "1") (pinfunction "1_1") (pintype "passive"))
      (node (ref "U3") (pin "4") (pinfunction "Y_4") (pintype "bidirectional"))
    )
    (net (code "38") (name "Net-(U4-Y)") (class "Default")
      (node (ref "D15") (pin "1") (pinfunction "1_1") (pintype "bidirectional"))
      (node (ref "R15") (pin "1") (pinfunction "1_1") (pintype "passive"))
      (node (ref "U4") (pin "4") (pinfunction "Y_4") (pintype "bidirectional"))
    )
    (net (code "39") (name "VCC") (class "Default")
      (node (ref "C14") (pin "2") (pinfunction "2_2") (pintype "passive"))
      (node (ref "C3") (pin "2") (pinfunction "2_2") (pintype "passive"))
      (node (ref "D2") (pin "1") (pinfunction "1_1") (pintype "bidirectional"))
      (node (ref "IC4") (pin "5") (pinfunction "VCC_5") (pintype "bidirectional"))
      (node (ref "J1") (pin "8") (pinfunction "3.3V_8") (pintype "power_in"))
      (node (ref "L2") (pin "1") (pinfunction "1_1") (pintype "passive"))
      (node (ref "R6") (pin "1") (pinfunction "1_1") (pintype "passive"))
    )
    (net (code "40") (name "VIN") (class "Default")
      (node (ref "D1") (pin "1") (pinfunction "K_1") (pintype "bidirectional"))
      (node (ref "J1") (pin "10") (pinfunction "VIN_10") (pintype "power_in"))
    )
    (net (code "41") (name "V_BATT") (class "Default")
      (node (ref "C13") (pin "2") (pinfunction "2_2") (pintype "passive"))
      (node (ref "C15") (pin "2") (pinfunction "2_2") (pintype "passive"))
      (node (ref "C16") (pin "2") (pinfunction "2_2") (pintype "passive"))
      (node (ref "C17") (pin "2") (pinfunction "2_2") (pintype "passive"))
      (node (ref "C18") (pin "2") (pinfunction "2_2") (pintype "passive"))
      (node (ref "C4") (pin "2") (pinfunction "2_2") (pintype "passive"))
      (node (ref "IC1") (pin "4") (pinfunction "VOUT_4") (pintype "bidirectional"))
      (node (ref "IC3") (pin "5") (pinfunction "V+_5") (pintype "input"))
      (node (ref "R5") (pin "1") (pinfunction "1_1") (pintype "passive"))
      (node (ref "U1") (pin "5") (pinfunction "VCC_5") (pintype "bidirectional"))
      (node (ref "U2") (pin "5") (pinfunction "VCC_5") (pintype "bidirectional"))
      (node (ref "U3") (pin "5") (pinfunction "VCC_5") (pintype "bidirectional"))
      (node (ref "U4") (pin "5") (pinfunction "VCC_5") (pintype "bidirectional"))
    )
    (net (code "42") (name "unconnected-(IC1-NC_1-Pad3)") (class "Default")
      (node (ref "IC1") (pin "3") (pinfunction "NC_1_3") (pintype "bidirectional"))
    )
    (net (code "43") (name "unconnected-(IC1-NC_2-Pad5)") (class "Default")
      (node (ref "IC1") (pin "5") (pinfunction "NC_2_5") (pintype "bidirectional"))
    )
    (net (code "44") (name "unconnected-(IC4-N.C.-Pad1)") (class "Default")
      (node (ref "IC4") (pin "1") (pinfunction "N.C._1") (pintype "no_connect"))
    )
    (net (code "45") (name "unconnected-(J1-MDI_LED-Pad17)") (class "Default")
      (node (ref "J1") (pin "17") (pinfunction "MDI_LED_17") (pintype "bidirectional"))
    )
    (net (code "46") (name "unconnected-(J1-MDI_RX_N-Pad18)") (class "Default")
      (node (ref "J1") (pin "18") (pinfunction "MDI_RX_N_18") (pintype "bidirectional"))
    )
    (net (code "47") (name "unconnected-(J1-MDI_RX_P-Pad19)") (class "Default")
      (node (ref "J1") (pin "19") (pinfunction "MDI_RX_P_19") (pintype "bidirectional"))
    )
    (net (code "48") (name "unconnected-(J1-MDI_TX_N-Pad20)") (class "Default")
      (node (ref "J1") (pin "20") (pinfunction "MDI_TX_N_20") (pintype "bidirectional"))
    )
    (net (code "49") (name "unconnected-(J1-MDI_TX_P-Pad21)") (class "Default")
      (node (ref "J1") (pin "21") (pinfunction "MDI_TX_P_21") (pintype "bidirectional"))
    )
    (net (code "50") (name "unconnected-(J1-ON{slash}OFF-Pad22)") (class "Default")
      (node (ref "J1") (pin "22") (pinfunction "ON/OFF_22") (pintype "bidirectional"))
    )
    (net (code "51") (name "unconnected-(J1-P0{slash}MOSI{slash}PWM-Pad1)") (class "Default")
      (node (ref "J1") (pin "1") (pinfunction "P0/MOSI/PWM_1") (pintype "bidirectional"))
    )
    (net (code "52") (name "unconnected-(J1-P1{slash}MISO{slash}CANTX-Pad2)") (class "Default")
      (node (ref "J1") (pin "2") (pinfunction "P1/MISO/CANTX_2") (pintype "bidirectional"))
    )
    (net (code "53") (name "unconnected-(J1-P2{slash}SCLK{slash}PWM-Pad3)") (class "Default")
      (node (ref "J1") (pin "3") (pinfunction "P2/SCLK/PWM_3") (pintype "bidirectional"))
    )
    (net (code "54") (name "unconnected-(J1-P3{slash}SSEL{slash}CANRX-Pad4)") (class "Default")
      (node (ref "J1") (pin "4") (pinfunction "P3/SSEL/CANRX_4") (pintype "bidirectional"))
    )
    (net (code "55") (name "unconnected-(J1-P4{slash}SCL{slash}TXD{slash}PWM{slash}ADC-Pad5)") (class "Default")
      (node (ref "J1") (pin "5") (pinfunction "P4/SCL/TXD/PWM/ADC_5") (pintype "bidirectional"))
    )
    (net (code "56") (name "unconnected-(J1-P5{slash}SDA{slash}RXD{slash}PWM{slash}ADC-Pad6)") (class "Default")
      (node (ref "J1") (pin "6") (pinfunction "P5/SDA/RXD/PWM/ADC_6") (pintype "bidirectional"))
    )
    (net (code "57") (name "unconnected-(J1-P11{slash}WAKE-Pad15)") (class "Default")
      (node (ref "J1") (pin "15") (pinfunction "P11/WAKE_15") (pintype "bidirectional"))
    )
    (net (code "58") (name "unconnected-(J1-P12{slash}RESET-Pad16)") (class "Default")
      (node (ref "J1") (pin "16") (pinfunction "P12/RESET_16") (pintype "bidirectional"))
    )
    (net (code "59") (name "unconnected-(U1-NC-Pad1)") (class "Default")
      (node (ref "U1") (pin "1") (pinfunction "NC_1") (pintype "no_connect"))
    )
    (net (code "60") (name "unconnected-(U2-NC-Pad1)") (class "Default")
      (node (ref "U2") (pin "1") (pinfunction "NC_1") (pintype "no_connect"))
    )
    (net (code "61") (name "unconnected-(U3-NC-Pad1)") (class "Default")
      (node (ref "U3") (pin "1") (pinfunction "NC_1") (pintype "no_connect"))
    )
    (net (code "62") (name "unconnected-(U4-NC-Pad1)") (class "Default")
      (node (ref "U4") (pin "1") (pinfunction "NC_1") (pintype "no_connect"))
    )
  )
)
